# icestampul1k.net
KiCad netlist of a schematic drawn in EAGLE
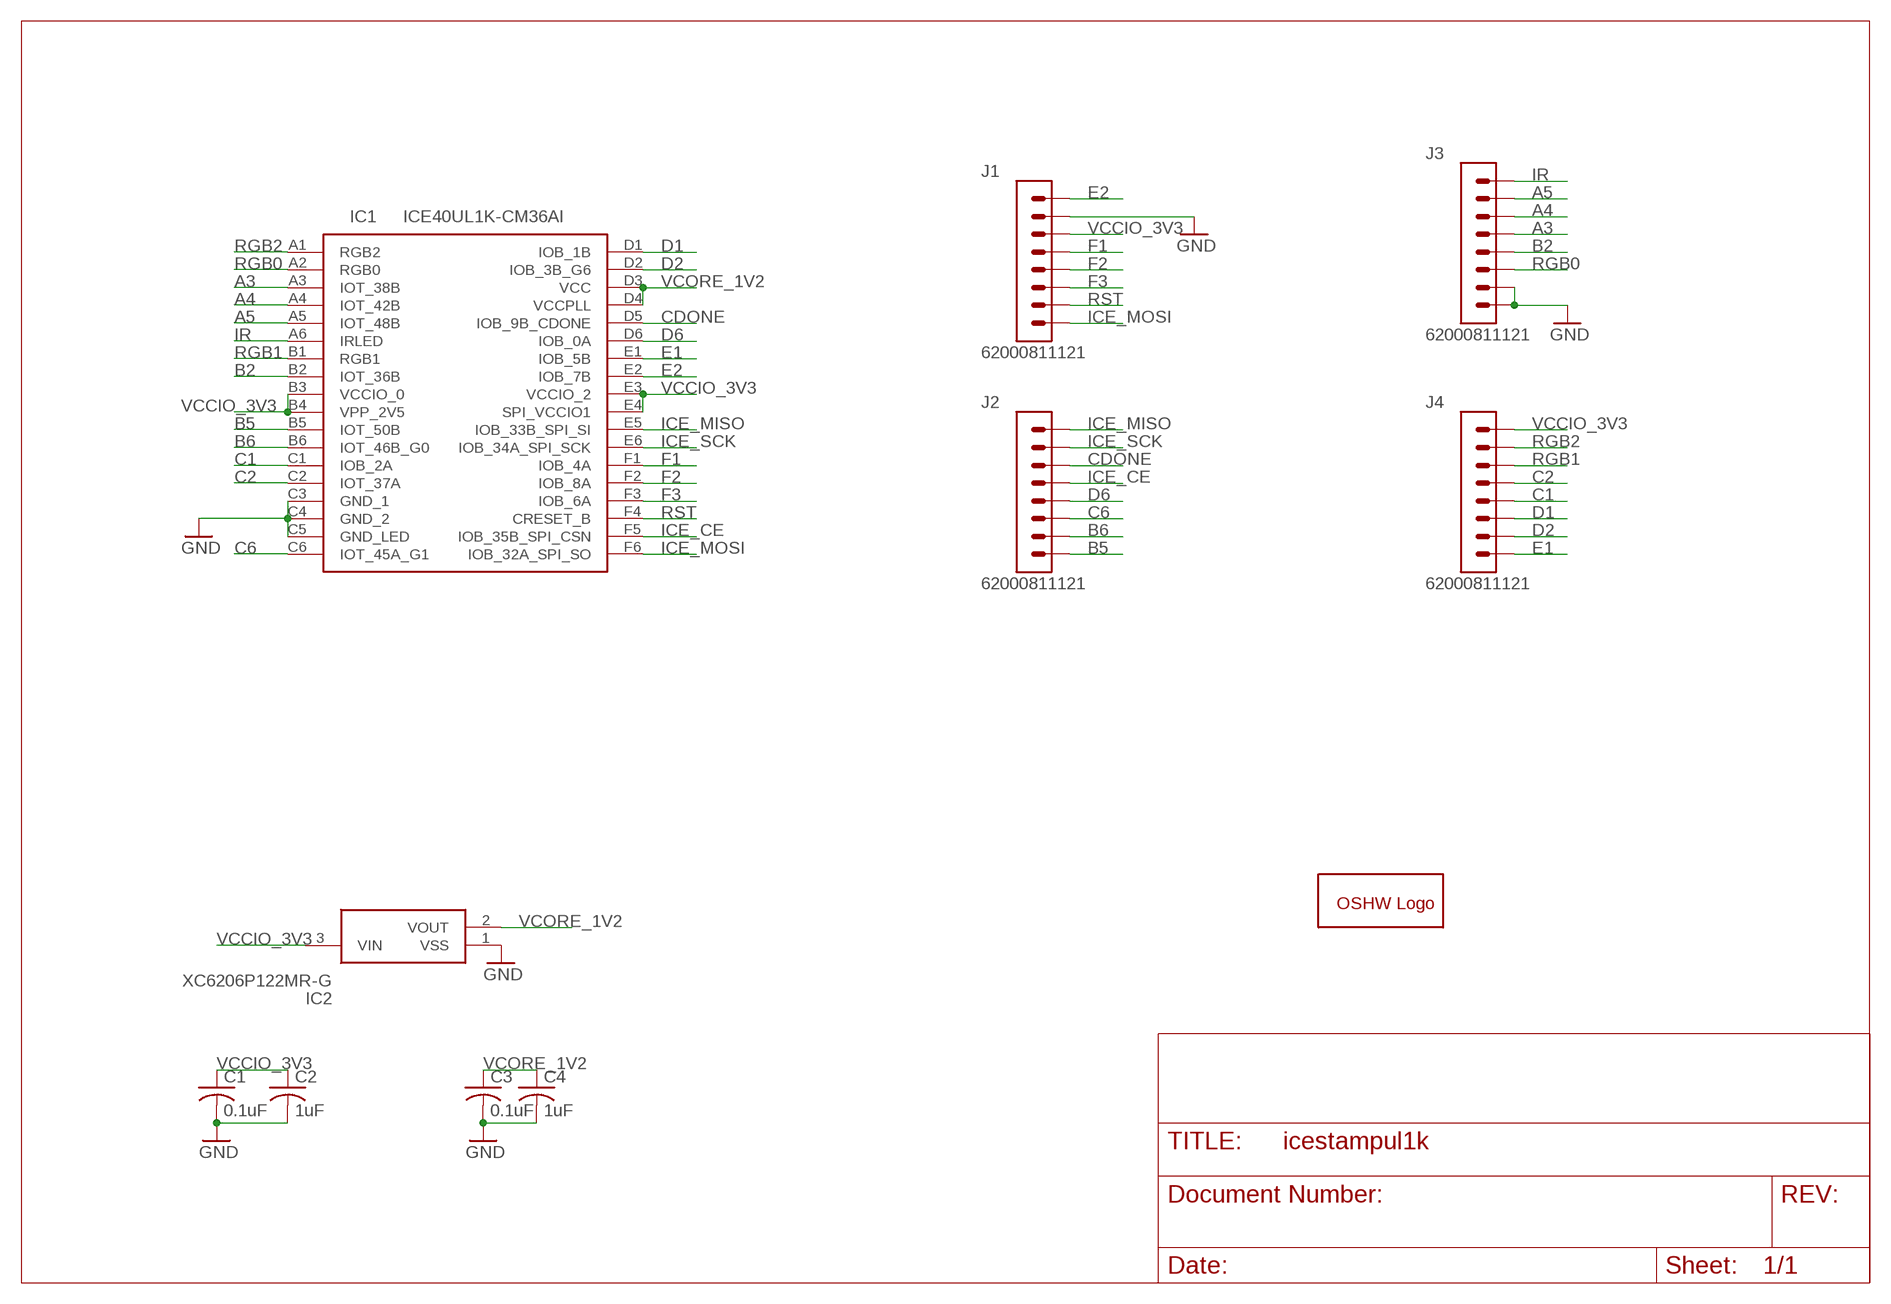
[diagram p0: schematic, sheet 1]

(export (version "E")
  (design (tool "Eeschema 10.0.6"))
  (components
    (comp (ref "C1")
      (value "0.1uF")
      (footprint "eagle-import:C0603")
      (libsource (lib "eagle-import") (part "C-USC0603"))
    )
    (comp (ref "C2")
      (value "1uF")
      (footprint "eagle-import:C0603")
      (libsource (lib "eagle-import") (part "C-USC0603"))
    )
    (comp (ref "C3")
      (value "0.1uF")
      (footprint "eagle-import:C0603")
      (libsource (lib "eagle-import") (part "C-USC0603"))
    )
    (comp (ref "C4")
      (value "1uF")
      (footprint "eagle-import:C0603")
      (libsource (lib "eagle-import") (part "C-USC0603"))
    )
    (comp (ref "GOLD_ORB_SM1")
      (value "OSHWLOGOLOGO5MM")
      (footprint "eagle-import:OSHW_5MM")
      (libsource (lib "eagle-import") (part "OSHWLOGOLOGO5MM"))
    )
    (comp (ref "IC1")
      (value "ICE40UL1K-CM36AI")
      (footprint "eagle-import:BGA36C40P6X6_250X250X91")
      (fields (field (name "MOUSER_PART_NUMBER") "842-ICE40UL1K-CM36AI"))
      (libsource (lib "eagle-import") (part "ICE40UL1K-CM36AI"))
    )
    (comp (ref "IC2")
      (value "XC6206P122MR-G")
      (footprint "eagle-import:SOT95P280X130-3N")
      (fields (field (name "MOUSER_PART_NUMBER") "865-XC6206P122MR-G"))
      (libsource (lib "eagle-import") (part "XC6206P122MR-G"))
    )
    (comp (ref "J1")
      (value "62000811121")
      (footprint "eagle-import:62000811121")
      (fields (field (name "MANUFACTURER") "Würth Elektronik ") (field (name "CREATED_BY") "PCBLayout.com"))
      (libsource (lib "eagle-import") (part "62000811121"))
    )
    (comp (ref "J2")
      (value "62000811121")
      (footprint "eagle-import:62000811121")
      (fields (field (name "MANUFACTURER") "Würth Elektronik ") (field (name "CREATED_BY") "PCBLayout.com"))
      (libsource (lib "eagle-import") (part "62000811121"))
    )
    (comp (ref "J3")
      (value "62000811121")
      (footprint "eagle-import:62000811121")
      (fields (field (name "MANUFACTURER") "Würth Elektronik ") (field (name "CREATED_BY") "PCBLayout.com"))
      (libsource (lib "eagle-import") (part "62000811121"))
    )
    (comp (ref "J4")
      (value "62000811121")
      (footprint "eagle-import:62000811121")
      (fields (field (name "MANUFACTURER") "Würth Elektronik ") (field (name "CREATED_BY") "PCBLayout.com"))
      (libsource (lib "eagle-import") (part "62000811121"))
    )
  )
  (nets
    (net (code "1") (name "/A3") (class "Default")
      (node (ref "IC1") (pin "A3") (pinfunction "IOT_38B_A3") (pintype "bidirectional"))
      (node (ref "J3") (pin "4") (pinfunction "4_4") (pintype "passive"))
    )
    (net (code "2") (name "/A4") (class "Default")
      (node (ref "IC1") (pin "A4") (pinfunction "IOT_42B_A4") (pintype "bidirectional"))
      (node (ref "J3") (pin "3") (pinfunction "3_3") (pintype "passive"))
    )
    (net (code "3") (name "/A5") (class "Default")
      (node (ref "IC1") (pin "A5") (pinfunction "IOT_48B_A5") (pintype "bidirectional"))
      (node (ref "J3") (pin "2") (pinfunction "2_2") (pintype "passive"))
    )
    (net (code "4") (name "/B2") (class "Default")
      (node (ref "IC1") (pin "B2") (pinfunction "IOT_36B_B2") (pintype "bidirectional"))
      (node (ref "J3") (pin "5") (pinfunction "5_5") (pintype "passive"))
    )
    (net (code "5") (name "/B5") (class "Default")
      (node (ref "IC1") (pin "B5") (pinfunction "IOT_50B_B5") (pintype "bidirectional"))
      (node (ref "J2") (pin "8") (pinfunction "8_8") (pintype "passive"))
    )
    (net (code "6") (name "/B6") (class "Default")
      (node (ref "IC1") (pin "B6") (pinfunction "IOT_46B_G0_B6") (pintype "bidirectional"))
      (node (ref "J2") (pin "7") (pinfunction "7_7") (pintype "passive"))
    )
    (net (code "7") (name "/C1") (class "Default")
      (node (ref "IC1") (pin "C1") (pinfunction "IOB_2A_C1") (pintype "bidirectional"))
      (node (ref "J4") (pin "5") (pinfunction "5_5") (pintype "passive"))
    )
    (net (code "8") (name "/C2") (class "Default")
      (node (ref "IC1") (pin "C2") (pinfunction "IOT_37A_C2") (pintype "bidirectional"))
      (node (ref "J4") (pin "4") (pinfunction "4_4") (pintype "passive"))
    )
    (net (code "9") (name "/C6") (class "Default")
      (node (ref "IC1") (pin "C6") (pinfunction "IOT_45A_G1_C6") (pintype "bidirectional"))
      (node (ref "J2") (pin "6") (pinfunction "6_6") (pintype "passive"))
    )
    (net (code "10") (name "/CDONE") (class "Default")
      (node (ref "IC1") (pin "D5") (pinfunction "IOB_9B_CDONE_D5") (pintype "bidirectional"))
      (node (ref "J2") (pin "3") (pinfunction "3_3") (pintype "passive"))
    )
    (net (code "11") (name "/D1") (class "Default")
      (node (ref "IC1") (pin "D1") (pinfunction "IOB_1B_D1") (pintype "bidirectional"))
      (node (ref "J4") (pin "6") (pinfunction "6_6") (pintype "passive"))
    )
    (net (code "12") (name "/D2") (class "Default")
      (node (ref "IC1") (pin "D2") (pinfunction "IOB_3B_G6_D2") (pintype "bidirectional"))
      (node (ref "J4") (pin "7") (pinfunction "7_7") (pintype "passive"))
    )
    (net (code "13") (name "/D6") (class "Default")
      (node (ref "IC1") (pin "D6") (pinfunction "IOB_0A_D6") (pintype "bidirectional"))
      (node (ref "J2") (pin "5") (pinfunction "5_5") (pintype "passive"))
    )
    (net (code "14") (name "/E1") (class "Default")
      (node (ref "IC1") (pin "E1") (pinfunction "IOB_5B_E1") (pintype "bidirectional"))
      (node (ref "J4") (pin "8") (pinfunction "8_8") (pintype "passive"))
    )
    (net (code "15") (name "/E2") (class "Default")
      (node (ref "IC1") (pin "E2") (pinfunction "IOB_7B_E2") (pintype "bidirectional"))
      (node (ref "J1") (pin "1") (pinfunction "1_1") (pintype "passive"))
    )
    (net (code "16") (name "/F1") (class "Default")
      (node (ref "IC1") (pin "F1") (pinfunction "IOB_4A_F1") (pintype "bidirectional"))
      (node (ref "J1") (pin "4") (pinfunction "4_4") (pintype "passive"))
    )
    (net (code "17") (name "/F2") (class "Default")
      (node (ref "IC1") (pin "F2") (pinfunction "IOB_8A_F2") (pintype "bidirectional"))
      (node (ref "J1") (pin "5") (pinfunction "5_5") (pintype "passive"))
    )
    (net (code "18") (name "/F3") (class "Default")
      (node (ref "IC1") (pin "F3") (pinfunction "IOB_6A_F3") (pintype "bidirectional"))
      (node (ref "J1") (pin "6") (pinfunction "6_6") (pintype "passive"))
    )
    (net (code "19") (name "/ICE_CE") (class "Default")
      (node (ref "IC1") (pin "F5") (pinfunction "IOB_35B_SPI_CSN_F5") (pintype "bidirectional"))
      (node (ref "J2") (pin "4") (pinfunction "4_4") (pintype "passive"))
    )
    (net (code "20") (name "/ICE_MISO") (class "Default")
      (node (ref "IC1") (pin "E5") (pinfunction "IOB_33B_SPI_SI_E5") (pintype "bidirectional"))
      (node (ref "J2") (pin "1") (pinfunction "1_1") (pintype "passive"))
    )
    (net (code "21") (name "/ICE_MOSI") (class "Default")
      (node (ref "IC1") (pin "F6") (pinfunction "IOB_32A_SPI_SO_F6") (pintype "bidirectional"))
      (node (ref "J1") (pin "8") (pinfunction "8_8") (pintype "passive"))
    )
    (net (code "22") (name "/ICE_SCK") (class "Default")
      (node (ref "IC1") (pin "E6") (pinfunction "IOB_34A_SPI_SCK_E6") (pintype "bidirectional"))
      (node (ref "J2") (pin "2") (pinfunction "2_2") (pintype "passive"))
    )
    (net (code "23") (name "/IR") (class "Default")
      (node (ref "IC1") (pin "A6") (pinfunction "IRLED_A6") (pintype "bidirectional"))
      (node (ref "J3") (pin "1") (pinfunction "1_1") (pintype "passive"))
    )
    (net (code "24") (name "/RGB0") (class "Default")
      (node (ref "IC1") (pin "A2") (pinfunction "RGB0_A2") (pintype "bidirectional"))
      (node (ref "J3") (pin "6") (pinfunction "6_6") (pintype "passive"))
    )
    (net (code "25") (name "/RGB1") (class "Default")
      (node (ref "IC1") (pin "B1") (pinfunction "RGB1_B1") (pintype "bidirectional"))
      (node (ref "J4") (pin "3") (pinfunction "3_3") (pintype "passive"))
    )
    (net (code "26") (name "/RGB2") (class "Default")
      (node (ref "IC1") (pin "A1") (pinfunction "RGB2_A1") (pintype "bidirectional"))
      (node (ref "J4") (pin "2") (pinfunction "2_2") (pintype "passive"))
    )
    (net (code "27") (name "/RST") (class "Default")
      (node (ref "IC1") (pin "F4") (pinfunction "CRESET_B_F4") (pintype "bidirectional"))
      (node (ref "J1") (pin "7") (pinfunction "7_7") (pintype "passive"))
    )
    (net (code "28") (name "/VCCIO_3V3") (class "Default")
      (node (ref "C1") (pin "1") (pinfunction "1_1") (pintype "passive"))
      (node (ref "C2") (pin "1") (pinfunction "1_1") (pintype "passive"))
      (node (ref "IC1") (pin "B3") (pinfunction "VCCIO_0_B3") (pintype "bidirectional"))
      (node (ref "IC1") (pin "B4") (pinfunction "VPP_2V5_B4") (pintype "bidirectional"))
      (node (ref "IC1") (pin "E3") (pinfunction "VCCIO_2_E3") (pintype "bidirectional"))
      (node (ref "IC1") (pin "E4") (pinfunction "SPI_VCCIO1_E4") (pintype "bidirectional"))
      (node (ref "IC2") (pin "3") (pinfunction "VIN_3") (pintype "bidirectional"))
      (node (ref "J1") (pin "3") (pinfunction "3_3") (pintype "passive"))
      (node (ref "J4") (pin "1") (pinfunction "1_1") (pintype "passive"))
    )
    (net (code "29") (name "/VCORE_1V2") (class "Default")
      (node (ref "C3") (pin "1") (pinfunction "1_1") (pintype "passive"))
      (node (ref "C4") (pin "1") (pinfunction "1_1") (pintype "passive"))
      (node (ref "IC1") (pin "D3") (pinfunction "VCC_D3") (pintype "bidirectional"))
      (node (ref "IC1") (pin "D4") (pinfunction "VCCPLL_D4") (pintype "bidirectional"))
      (node (ref "IC2") (pin "2") (pinfunction "VOUT_2") (pintype "bidirectional"))
    )
    (net (code "30") (name "GND") (class "Default")
      (node (ref "C1") (pin "2") (pinfunction "2_2") (pintype "passive"))
      (node (ref "C2") (pin "2") (pinfunction "2_2") (pintype "passive"))
      (node (ref "C3") (pin "2") (pinfunction "2_2") (pintype "passive"))
      (node (ref "C4") (pin "2") (pinfunction "2_2") (pintype "passive"))
      (node (ref "IC1") (pin "C3") (pinfunction "GND_1_C3") (pintype "bidirectional"))
      (node (ref "IC1") (pin "C4") (pinfunction "GND_2_C4") (pintype "bidirectional"))
      (node (ref "IC1") (pin "C5") (pinfunction "GND_LED_C5") (pintype "bidirectional"))
      (node (ref "IC2") (pin "1") (pinfunction "VSS_1") (pintype "bidirectional"))
      (node (ref "J1") (pin "2") (pinfunction "2_2") (pintype "passive"))
      (node (ref "J3") (pin "7") (pinfunction "7_7") (pintype "passive"))
      (node (ref "J3") (pin "8") (pinfunction "8_8") (pintype "passive"))
    )
  )
)
